# board.net
KiCad netlist of a schematic drawn in EAGLE
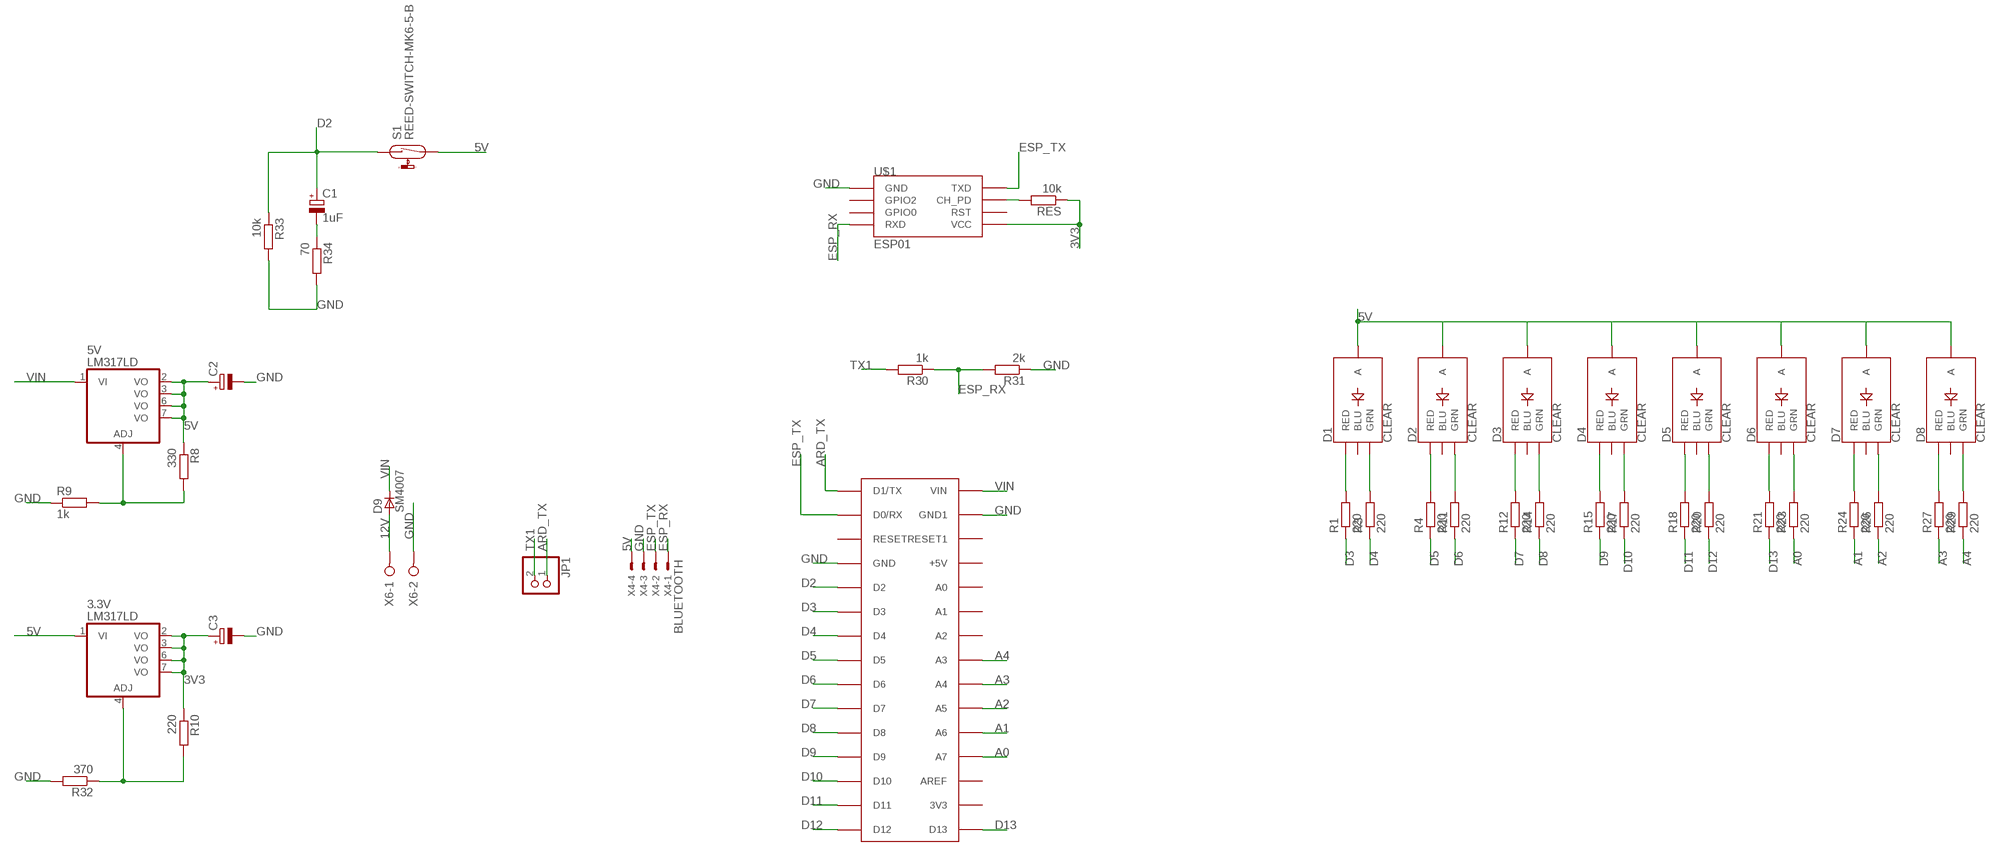
[diagram p0: schematic, sheet 1]

(export (version "E")
  (design (tool "Eeschema 10.0.6"))
  (components
    (comp (ref "3.3V")
      (value "LM317LD")
      (footprint "eagle-import:SO08")
      (libsource (lib "eagle-import") (part "LM317LD"))
    )
    (comp (ref "5V")
      (value "LM317LD")
      (footprint "eagle-import:SO08")
      (libsource (lib "eagle-import") (part "LM317LD"))
    )
    (comp (ref "C1")
      (value "1uF")
      (footprint "eagle-import:E2-4")
      (libsource (lib "eagle-import") (part "CPOL-EUE2-4"))
    )
    (comp (ref "C2")
      (value "CPOL-EUE2-5")
      (footprint "eagle-import:E2-5")
      (libsource (lib "eagle-import") (part "rcl_334_CPOL-EUE2-5"))
    )
    (comp (ref "C3")
      (value "CPOL-EUE2-5")
      (footprint "eagle-import:E2-5")
      (libsource (lib "eagle-import") (part "rcl_334_CPOL-EUE2-5"))
    )
    (comp (ref "D1")
      (value "CLEAR")
      (footprint "eagle-import:LED-RGB-THRU")
      (libsource (lib "eagle-import") (part "LED-RGB-CACLEAR"))
    )
    (comp (ref "D2")
      (value "CLEAR")
      (footprint "eagle-import:LED-RGB-THRU")
      (libsource (lib "eagle-import") (part "LED-RGB-CACLEAR"))
    )
    (comp (ref "D3")
      (value "CLEAR")
      (footprint "eagle-import:LED-RGB-THRU")
      (libsource (lib "eagle-import") (part "LED-RGB-CACLEAR"))
    )
    (comp (ref "D4")
      (value "CLEAR")
      (footprint "eagle-import:LED-RGB-THRU")
      (libsource (lib "eagle-import") (part "LED-RGB-CACLEAR"))
    )
    (comp (ref "D5")
      (value "CLEAR")
      (footprint "eagle-import:LED-RGB-THRU")
      (libsource (lib "eagle-import") (part "LED-RGB-CACLEAR"))
    )
    (comp (ref "D6")
      (value "CLEAR")
      (footprint "eagle-import:LED-RGB-THRU")
      (libsource (lib "eagle-import") (part "LED-RGB-CACLEAR"))
    )
    (comp (ref "D7")
      (value "CLEAR")
      (footprint "eagle-import:LED-RGB-THRU")
      (libsource (lib "eagle-import") (part "LED-RGB-CACLEAR"))
    )
    (comp (ref "D8")
      (value "CLEAR")
      (footprint "eagle-import:LED-RGB-THRU")
      (libsource (lib "eagle-import") (part "LED-RGB-CACLEAR"))
    )
    (comp (ref "D9")
      (value "SM4007")
      (footprint "eagle-import:MELF-MLL41_DO213AB")
      (libsource (lib "eagle-import") (part "SM4007"))
    )
    (comp (ref "JP1")
      (value "PINHD-1X2")
      (footprint "eagle-import:1X02")
      (libsource (lib "eagle-import") (part "PINHD-1X2"))
    )
    (comp (ref "R1")
      (value "220")
      (footprint "eagle-import:R1206")
      (libsource (lib "eagle-import") (part "R-EU_R1206"))
    )
    (comp (ref "R3")
      (value "220")
      (footprint "eagle-import:R1206")
      (libsource (lib "eagle-import") (part "R-EU_R1206"))
    )
    (comp (ref "R4")
      (value "220")
      (footprint "eagle-import:R1206")
      (libsource (lib "eagle-import") (part "R-EU_R1206"))
    )
    (comp (ref "R8")
      (value "330")
      (footprint "eagle-import:R1206")
      (libsource (lib "eagle-import") (part "R-EU_R1206"))
    )
    (comp (ref "R9")
      (value "1k")
      (footprint "eagle-import:R1206")
      (libsource (lib "eagle-import") (part "R-EU_R1206"))
    )
    (comp (ref "R10")
      (value "220")
      (footprint "eagle-import:R1206")
      (libsource (lib "eagle-import") (part "R-EU_R1206"))
    )
    (comp (ref "R11")
      (value "220")
      (footprint "eagle-import:R1206")
      (libsource (lib "eagle-import") (part "R-EU_R1206"))
    )
    (comp (ref "R12")
      (value "220")
      (footprint "eagle-import:R1206")
      (libsource (lib "eagle-import") (part "R-EU_R1206"))
    )
    (comp (ref "R14")
      (value "220")
      (footprint "eagle-import:R1206")
      (libsource (lib "eagle-import") (part "R-EU_R1206"))
    )
    (comp (ref "R15")
      (value "220")
      (footprint "eagle-import:R1206")
      (libsource (lib "eagle-import") (part "R-EU_R1206"))
    )
    (comp (ref "R17")
      (value "220")
      (footprint "eagle-import:R1206")
      (libsource (lib "eagle-import") (part "R-EU_R1206"))
    )
    (comp (ref "R18")
      (value "220")
      (footprint "eagle-import:R1206")
      (libsource (lib "eagle-import") (part "R-EU_R1206"))
    )
    (comp (ref "R20")
      (value "220")
      (footprint "eagle-import:R1206")
      (libsource (lib "eagle-import") (part "R-EU_R1206"))
    )
    (comp (ref "R21")
      (value "220")
      (footprint "eagle-import:R1206")
      (libsource (lib "eagle-import") (part "R-EU_R1206"))
    )
    (comp (ref "R23")
      (value "220")
      (footprint "eagle-import:R1206")
      (libsource (lib "eagle-import") (part "R-EU_R1206"))
    )
    (comp (ref "R24")
      (value "220")
      (footprint "eagle-import:R1206")
      (libsource (lib "eagle-import") (part "R-EU_R1206"))
    )
    (comp (ref "R26")
      (value "220")
      (footprint "eagle-import:R1206")
      (libsource (lib "eagle-import") (part "R-EU_R1206"))
    )
    (comp (ref "R27")
      (value "220")
      (footprint "eagle-import:R1206")
      (libsource (lib "eagle-import") (part "R-EU_R1206"))
    )
    (comp (ref "R29")
      (value "220")
      (footprint "eagle-import:R1206")
      (libsource (lib "eagle-import") (part "R-EU_R1206"))
    )
    (comp (ref "R30")
      (value "1k")
      (footprint "eagle-import:R1206")
      (libsource (lib "eagle-import") (part "R-EU_R1206"))
    )
    (comp (ref "R31")
      (value "2k")
      (footprint "eagle-import:R1206")
      (libsource (lib "eagle-import") (part "R-EU_R1206"))
    )
    (comp (ref "R32")
      (value "370")
      (footprint "eagle-import:R1206")
      (libsource (lib "eagle-import") (part "R-EU_R1206"))
    )
    (comp (ref "R33")
      (value "10k")
      (footprint "eagle-import:R1206")
      (libsource (lib "eagle-import") (part "R-EU_R1206"))
    )
    (comp (ref "R34")
      (value "70")
      (footprint "eagle-import:R1206")
      (libsource (lib "eagle-import") (part "R-EU_R1206"))
    )
    (comp (ref "RES")
      (value "10k")
      (footprint "eagle-import:R1206")
      (libsource (lib "eagle-import") (part "R-EU_R1206"))
    )
    (comp (ref "S1")
      (value "REED-SWITCH-MK6-5-B")
      (footprint "eagle-import:MK6-5")
      (fields (field (name "MF") "MEDER") (field (name "MPN") "MK6-5-B"))
      (libsource (lib "eagle-import") (part "REED-SWITCH-MK6-5-B"))
    )
    (comp (ref "U$1")
      (value "ESP01")
      (footprint "eagle-import:ESP01")
      (libsource (lib "eagle-import") (part "ESP01"))
    )
    (comp (ref "U$2")
      (value "ARDUINONANO")
      (footprint "eagle-import:PDIP-32")
      (libsource (lib "eagle-import") (part "ARDUINONANO"))
    )
    (comp (ref "X4")
      (value "BLUETOOTH")
      (footprint "eagle-import:22-23-2041")
      (fields (field (name "MF") "MOLEX") (field (name "MPN") "22-23-2041"))
      (libsource (lib "eagle-import") (part "22-23-2041"))
    )
    (comp (ref "X6")
      (value "W237-02P")
      (footprint "eagle-import:W237-132")
      (libsource (lib "eagle-import") (part "W237-02P"))
    )
  )
  (nets
    (net (code "1") (name "/3V3") (class "Default")
      (node (ref "3.3V") (pin "2") (pinfunction "VO_2") (pintype "passive"))
      (node (ref "3.3V") (pin "3") (pinfunction "VO_3") (pintype "passive"))
      (node (ref "3.3V") (pin "6") (pinfunction "VO_6") (pintype "passive"))
      (node (ref "3.3V") (pin "7") (pinfunction "VO_7") (pintype "passive"))
      (node (ref "C3") (pin "+") (pinfunction "+_+") (pintype "passive"))
      (node (ref "R10") (pin "1") (pinfunction "1_1") (pintype "passive"))
      (node (ref "RES") (pin "1") (pinfunction "1_1") (pintype "passive"))
      (node (ref "U$1") (pin "VCC") (pinfunction "VCC_VCC") (pintype "bidirectional"))
    )
    (net (code "2") (name "/5V") (class "Default")
      (node (ref "3.3V") (pin "1") (pinfunction "VI_1") (pintype "input"))
      (node (ref "5V") (pin "2") (pinfunction "VO_2") (pintype "passive"))
      (node (ref "5V") (pin "3") (pinfunction "VO_3") (pintype "passive"))
      (node (ref "5V") (pin "6") (pinfunction "VO_6") (pintype "passive"))
      (node (ref "5V") (pin "7") (pinfunction "VO_7") (pintype "passive"))
      (node (ref "C2") (pin "+") (pinfunction "+_+") (pintype "passive"))
      (node (ref "D1") (pin "2") (pinfunction "A_2") (pintype "bidirectional"))
      (node (ref "D2") (pin "2") (pinfunction "A_2") (pintype "bidirectional"))
      (node (ref "D3") (pin "2") (pinfunction "A_2") (pintype "bidirectional"))
      (node (ref "D4") (pin "2") (pinfunction "A_2") (pintype "bidirectional"))
      (node (ref "D5") (pin "2") (pinfunction "A_2") (pintype "bidirectional"))
      (node (ref "D6") (pin "2") (pinfunction "A_2") (pintype "bidirectional"))
      (node (ref "D7") (pin "2") (pinfunction "A_2") (pintype "bidirectional"))
      (node (ref "D8") (pin "2") (pinfunction "A_2") (pintype "bidirectional"))
      (node (ref "R8") (pin "1") (pinfunction "1_1") (pintype "passive"))
      (node (ref "S1") (pin "2") (pinfunction "2_2") (pintype "passive"))
      (node (ref "X4") (pin "4") (pinfunction "S_4") (pintype "passive"))
    )
    (net (code "3") (name "/12V") (class "Default")
      (node (ref "D9") (pin "A") (pinfunction "A_A") (pintype "passive"))
      (node (ref "X6") (pin "1") (pinfunction "KL_1") (pintype "passive"))
    )
    (net (code "4") (name "/A0") (class "Default")
      (node (ref "R23") (pin "1") (pinfunction "1_1") (pintype "passive"))
      (node (ref "U$2") (pin "A7") (pinfunction "A7_A7") (pintype "bidirectional"))
    )
    (net (code "5") (name "/A1") (class "Default")
      (node (ref "R24") (pin "1") (pinfunction "1_1") (pintype "passive"))
      (node (ref "U$2") (pin "A6") (pinfunction "A6_A6") (pintype "bidirectional"))
    )
    (net (code "6") (name "/A2") (class "Default")
      (node (ref "R26") (pin "1") (pinfunction "1_1") (pintype "passive"))
      (node (ref "U$2") (pin "A5") (pinfunction "A5_A5") (pintype "bidirectional"))
    )
    (net (code "7") (name "/A3") (class "Default")
      (node (ref "R27") (pin "1") (pinfunction "1_1") (pintype "passive"))
      (node (ref "U$2") (pin "A4") (pinfunction "A4_A4") (pintype "bidirectional"))
    )
    (net (code "8") (name "/A4") (class "Default")
      (node (ref "R29") (pin "1") (pinfunction "1_1") (pintype "passive"))
      (node (ref "U$2") (pin "A3") (pinfunction "A3_A3") (pintype "bidirectional"))
    )
    (net (code "9") (name "/ARD_TX") (class "Default")
      (node (ref "JP1") (pin "1") (pinfunction "1_1") (pintype "passive"))
      (node (ref "U$2") (pin "D1/TX") (pinfunction "D1/TX_D1/TX") (pintype "bidirectional"))
    )
    (net (code "10") (name "/D2") (class "Default")
      (node (ref "C1") (pin "+") (pinfunction "+_+") (pintype "passive"))
      (node (ref "R33") (pin "1") (pinfunction "1_1") (pintype "passive"))
      (node (ref "S1") (pin "1") (pinfunction "1_1") (pintype "passive"))
      (node (ref "U$2") (pin "D2") (pinfunction "D2_D2") (pintype "bidirectional"))
    )
    (net (code "11") (name "/D3") (class "Default")
      (node (ref "R1") (pin "1") (pinfunction "1_1") (pintype "passive"))
      (node (ref "U$2") (pin "D3") (pinfunction "D3_D3") (pintype "bidirectional"))
    )
    (net (code "12") (name "/D4") (class "Default")
      (node (ref "R3") (pin "1") (pinfunction "1_1") (pintype "passive"))
      (node (ref "U$2") (pin "D4") (pinfunction "D4_D4") (pintype "bidirectional"))
    )
    (net (code "13") (name "/D5") (class "Default")
      (node (ref "R4") (pin "1") (pinfunction "1_1") (pintype "passive"))
      (node (ref "U$2") (pin "D5") (pinfunction "D5_D5") (pintype "bidirectional"))
    )
    (net (code "14") (name "/D6") (class "Default")
      (node (ref "R11") (pin "1") (pinfunction "1_1") (pintype "passive"))
      (node (ref "U$2") (pin "D6") (pinfunction "D6_D6") (pintype "bidirectional"))
    )
    (net (code "15") (name "/D7") (class "Default")
      (node (ref "R12") (pin "1") (pinfunction "1_1") (pintype "passive"))
      (node (ref "U$2") (pin "D7") (pinfunction "D7_D7") (pintype "bidirectional"))
    )
    (net (code "16") (name "/D8") (class "Default")
      (node (ref "R14") (pin "1") (pinfunction "1_1") (pintype "passive"))
      (node (ref "U$2") (pin "D8") (pinfunction "D8_D8") (pintype "bidirectional"))
    )
    (net (code "17") (name "/D9") (class "Default")
      (node (ref "R15") (pin "1") (pinfunction "1_1") (pintype "passive"))
      (node (ref "U$2") (pin "D9") (pinfunction "D9_D9") (pintype "bidirectional"))
    )
    (net (code "18") (name "/D10") (class "Default")
      (node (ref "R17") (pin "1") (pinfunction "1_1") (pintype "passive"))
      (node (ref "U$2") (pin "D10") (pinfunction "D10_D10") (pintype "bidirectional"))
    )
    (net (code "19") (name "/D11") (class "Default")
      (node (ref "R18") (pin "1") (pinfunction "1_1") (pintype "passive"))
      (node (ref "U$2") (pin "D11") (pinfunction "D11_D11") (pintype "bidirectional"))
    )
    (net (code "20") (name "/D12") (class "Default")
      (node (ref "R20") (pin "1") (pinfunction "1_1") (pintype "passive"))
      (node (ref "U$2") (pin "D12") (pinfunction "D12_D12") (pintype "bidirectional"))
    )
    (net (code "21") (name "/D13") (class "Default")
      (node (ref "R21") (pin "1") (pinfunction "1_1") (pintype "passive"))
      (node (ref "U$2") (pin "D13") (pinfunction "D13_D13") (pintype "bidirectional"))
    )
    (net (code "22") (name "/ESP_RX") (class "Default")
      (node (ref "R30") (pin "1") (pinfunction "1_1") (pintype "passive"))
      (node (ref "R31") (pin "2") (pinfunction "2_2") (pintype "passive"))
      (node (ref "U$1") (pin "RX") (pinfunction "RXD_RX") (pintype "bidirectional"))
      (node (ref "X4") (pin "1") (pinfunction "S_1") (pintype "passive"))
    )
    (net (code "23") (name "/ESP_TX") (class "Default")
      (node (ref "U$1") (pin "TX") (pinfunction "TXD_TX") (pintype "bidirectional"))
      (node (ref "U$2") (pin "D0/RX") (pinfunction "D0/RX_D0/RX") (pintype "bidirectional"))
      (node (ref "X4") (pin "2") (pinfunction "S_2") (pintype "passive"))
    )
    (net (code "24") (name "/GND") (class "Default")
      (node (ref "C2") (pin "-") (pinfunction "-_-") (pintype "passive"))
      (node (ref "C3") (pin "-") (pinfunction "-_-") (pintype "passive"))
      (node (ref "R31") (pin "1") (pinfunction "1_1") (pintype "passive"))
      (node (ref "R32") (pin "2") (pinfunction "2_2") (pintype "passive"))
      (node (ref "R33") (pin "2") (pinfunction "2_2") (pintype "passive"))
      (node (ref "R34") (pin "2") (pinfunction "2_2") (pintype "passive"))
      (node (ref "R9") (pin "1") (pinfunction "1_1") (pintype "passive"))
      (node (ref "U$1") (pin "GND") (pinfunction "GND_GND") (pintype "bidirectional"))
      (node (ref "U$2") (pin "GND") (pinfunction "GND_GND") (pintype "bidirectional"))
      (node (ref "U$2") (pin "GND1") (pinfunction "GND1_GND1") (pintype "bidirectional"))
      (node (ref "X4") (pin "3") (pinfunction "S_3") (pintype "passive"))
      (node (ref "X6") (pin "2") (pinfunction "KL_2") (pintype "passive"))
    )
    (net (code "25") (name "/TX1") (class "Default")
      (node (ref "JP1") (pin "2") (pinfunction "2_2") (pintype "passive"))
      (node (ref "R30") (pin "2") (pinfunction "2_2") (pintype "passive"))
    )
    (net (code "26") (name "/VIN") (class "Default")
      (node (ref "5V") (pin "1") (pinfunction "VI_1") (pintype "input"))
      (node (ref "D9") (pin "C") (pinfunction "C_C") (pintype "passive"))
      (node (ref "U$2") (pin "VIN") (pinfunction "VIN_VIN") (pintype "bidirectional"))
    )
    (net (code "27") (name "Net-(3.3V-ADJ)") (class "Default")
      (node (ref "3.3V") (pin "4") (pinfunction "ADJ_4") (pintype "input"))
      (node (ref "R10") (pin "2") (pinfunction "2_2") (pintype "passive"))
      (node (ref "R32") (pin "1") (pinfunction "1_1") (pintype "passive"))
    )
    (net (code "28") (name "Net-(5V-ADJ)") (class "Default")
      (node (ref "5V") (pin "4") (pinfunction "ADJ_4") (pintype "input"))
      (node (ref "R8") (pin "2") (pinfunction "2_2") (pintype "passive"))
      (node (ref "R9") (pin "2") (pinfunction "2_2") (pintype "passive"))
    )
    (net (code "29") (name "Net-(C1-Pad-)") (class "Default")
      (node (ref "C1") (pin "-") (pinfunction "-_-") (pintype "passive"))
      (node (ref "R34") (pin "1") (pinfunction "1_1") (pintype "passive"))
    )
    (net (code "30") (name "Net-(D1-GRN)") (class "Default")
      (node (ref "D1") (pin "3") (pinfunction "GRN_3") (pintype "bidirectional"))
      (node (ref "R3") (pin "2") (pinfunction "2_2") (pintype "passive"))
    )
    (net (code "31") (name "Net-(D1-RED)") (class "Default")
      (node (ref "D1") (pin "1") (pinfunction "RED_1") (pintype "bidirectional"))
      (node (ref "R1") (pin "2") (pinfunction "2_2") (pintype "passive"))
    )
    (net (code "32") (name "Net-(D2-GRN)") (class "Default")
      (node (ref "D2") (pin "3") (pinfunction "GRN_3") (pintype "bidirectional"))
      (node (ref "R11") (pin "2") (pinfunction "2_2") (pintype "passive"))
    )
    (net (code "33") (name "Net-(D2-RED)") (class "Default")
      (node (ref "D2") (pin "1") (pinfunction "RED_1") (pintype "bidirectional"))
      (node (ref "R4") (pin "2") (pinfunction "2_2") (pintype "passive"))
    )
    (net (code "34") (name "Net-(D3-GRN)") (class "Default")
      (node (ref "D3") (pin "3") (pinfunction "GRN_3") (pintype "bidirectional"))
      (node (ref "R14") (pin "2") (pinfunction "2_2") (pintype "passive"))
    )
    (net (code "35") (name "Net-(D3-RED)") (class "Default")
      (node (ref "D3") (pin "1") (pinfunction "RED_1") (pintype "bidirectional"))
      (node (ref "R12") (pin "2") (pinfunction "2_2") (pintype "passive"))
    )
    (net (code "36") (name "Net-(D4-GRN)") (class "Default")
      (node (ref "D4") (pin "3") (pinfunction "GRN_3") (pintype "bidirectional"))
      (node (ref "R17") (pin "2") (pinfunction "2_2") (pintype "passive"))
    )
    (net (code "37") (name "Net-(D4-RED)") (class "Default")
      (node (ref "D4") (pin "1") (pinfunction "RED_1") (pintype "bidirectional"))
      (node (ref "R15") (pin "2") (pinfunction "2_2") (pintype "passive"))
    )
    (net (code "38") (name "Net-(D5-GRN)") (class "Default")
      (node (ref "D5") (pin "3") (pinfunction "GRN_3") (pintype "bidirectional"))
      (node (ref "R20") (pin "2") (pinfunction "2_2") (pintype "passive"))
    )
    (net (code "39") (name "Net-(D5-RED)") (class "Default")
      (node (ref "D5") (pin "1") (pinfunction "RED_1") (pintype "bidirectional"))
      (node (ref "R18") (pin "2") (pinfunction "2_2") (pintype "passive"))
    )
    (net (code "40") (name "Net-(D6-GRN)") (class "Default")
      (node (ref "D6") (pin "3") (pinfunction "GRN_3") (pintype "bidirectional"))
      (node (ref "R23") (pin "2") (pinfunction "2_2") (pintype "passive"))
    )
    (net (code "41") (name "Net-(D6-RED)") (class "Default")
      (node (ref "D6") (pin "1") (pinfunction "RED_1") (pintype "bidirectional"))
      (node (ref "R21") (pin "2") (pinfunction "2_2") (pintype "passive"))
    )
    (net (code "42") (name "Net-(D7-GRN)") (class "Default")
      (node (ref "D7") (pin "3") (pinfunction "GRN_3") (pintype "bidirectional"))
      (node (ref "R26") (pin "2") (pinfunction "2_2") (pintype "passive"))
    )
    (net (code "43") (name "Net-(D7-RED)") (class "Default")
      (node (ref "D7") (pin "1") (pinfunction "RED_1") (pintype "bidirectional"))
      (node (ref "R24") (pin "2") (pinfunction "2_2") (pintype "passive"))
    )
    (net (code "44") (name "Net-(D8-GRN)") (class "Default")
      (node (ref "D8") (pin "3") (pinfunction "GRN_3") (pintype "bidirectional"))
      (node (ref "R29") (pin "2") (pinfunction "2_2") (pintype "passive"))
    )
    (net (code "45") (name "Net-(D8-RED)") (class "Default")
      (node (ref "D8") (pin "1") (pinfunction "RED_1") (pintype "bidirectional"))
      (node (ref "R27") (pin "2") (pinfunction "2_2") (pintype "passive"))
    )
    (net (code "46") (name "Net-(RES-Pad2)") (class "Default")
      (node (ref "RES") (pin "2") (pinfunction "2_2") (pintype "passive"))
      (node (ref "U$1") (pin "CH_PD") (pinfunction "CH_PD_CH_PD") (pintype "bidirectional"))
    )
    (net (code "47") (name "unconnected-(D1-BLU-Pad4)") (class "Default")
      (node (ref "D1") (pin "4") (pinfunction "BLU_4") (pintype "bidirectional"))
    )
    (net (code "48") (name "unconnected-(D2-BLU-Pad4)") (class "Default")
      (node (ref "D2") (pin "4") (pinfunction "BLU_4") (pintype "bidirectional"))
    )
    (net (code "49") (name "unconnected-(D3-BLU-Pad4)") (class "Default")
      (node (ref "D3") (pin "4") (pinfunction "BLU_4") (pintype "bidirectional"))
    )
    (net (code "50") (name "unconnected-(D4-BLU-Pad4)") (class "Default")
      (node (ref "D4") (pin "4") (pinfunction "BLU_4") (pintype "bidirectional"))
    )
    (net (code "51") (name "unconnected-(D5-BLU-Pad4)") (class "Default")
      (node (ref "D5") (pin "4") (pinfunction "BLU_4") (pintype "bidirectional"))
    )
    (net (code "52") (name "unconnected-(D6-BLU-Pad4)") (class "Default")
      (node (ref "D6") (pin "4") (pinfunction "BLU_4") (pintype "bidirectional"))
    )
    (net (code "53") (name "unconnected-(D7-BLU-Pad4)") (class "Default")
      (node (ref "D7") (pin "4") (pinfunction "BLU_4") (pintype "bidirectional"))
    )
    (net (code "54") (name "unconnected-(D8-BLU-Pad4)") (class "Default")
      (node (ref "D8") (pin "4") (pinfunction "BLU_4") (pintype "bidirectional"))
    )
    (net (code "55") (name "unconnected-(U$1-PadGPIO0)") (class "Default")
      (node (ref "U$1") (pin "GPIO0") (pinfunction "GPIO0_GPIO0") (pintype "bidirectional"))
    )
    (net (code "56") (name "unconnected-(U$1-PadGPIO2)") (class "Default")
      (node (ref "U$1") (pin "GPIO2") (pinfunction "GPIO2_GPIO2") (pintype "bidirectional"))
    )
    (net (code "57") (name "unconnected-(U$1-PadRST)") (class "Default")
      (node (ref "U$1") (pin "RST") (pinfunction "RST_RST") (pintype "bidirectional"))
    )
    (net (code "58") (name "unconnected-(U$2-Pad+5V)") (class "Default")
      (node (ref "U$2") (pin "+5V") (pinfunction "+5V_+5V") (pintype "bidirectional"))
    )
    (net (code "59") (name "unconnected-(U$2-Pad3V3)") (class "Default")
      (node (ref "U$2") (pin "3V3") (pinfunction "3V3_3V3") (pintype "bidirectional"))
    )
    (net (code "60") (name "unconnected-(U$2-PadA0)") (class "Default")
      (node (ref "U$2") (pin "A0") (pinfunction "A0_A0") (pintype "bidirectional"))
    )
    (net (code "61") (name "unconnected-(U$2-PadA1)") (class "Default")
      (node (ref "U$2") (pin "A1") (pinfunction "A1_A1") (pintype "bidirectional"))
    )
    (net (code "62") (name "unconnected-(U$2-PadA2)") (class "Default")
      (node (ref "U$2") (pin "A2") (pinfunction "A2_A2") (pintype "bidirectional"))
    )
    (net (code "63") (name "unconnected-(U$2-PadAREF)") (class "Default")
      (node (ref "U$2") (pin "AREF") (pinfunction "AREF_AREF") (pintype "bidirectional"))
    )
    (net (code "64") (name "unconnected-(U$2-PadRESET)") (class "Default")
      (node (ref "U$2") (pin "RESET") (pinfunction "RESET_RESET") (pintype "bidirectional"))
    )
    (net (code "65") (name "unconnected-(U$2-PadRESET1)") (class "Default")
      (node (ref "U$2") (pin "RESET1") (pinfunction "RESET1_RESET1") (pintype "bidirectional"))
    )
  )
)
